# FRONT-UNIT-7.net
KiCad netlist of a schematic drawn in Altium Designer
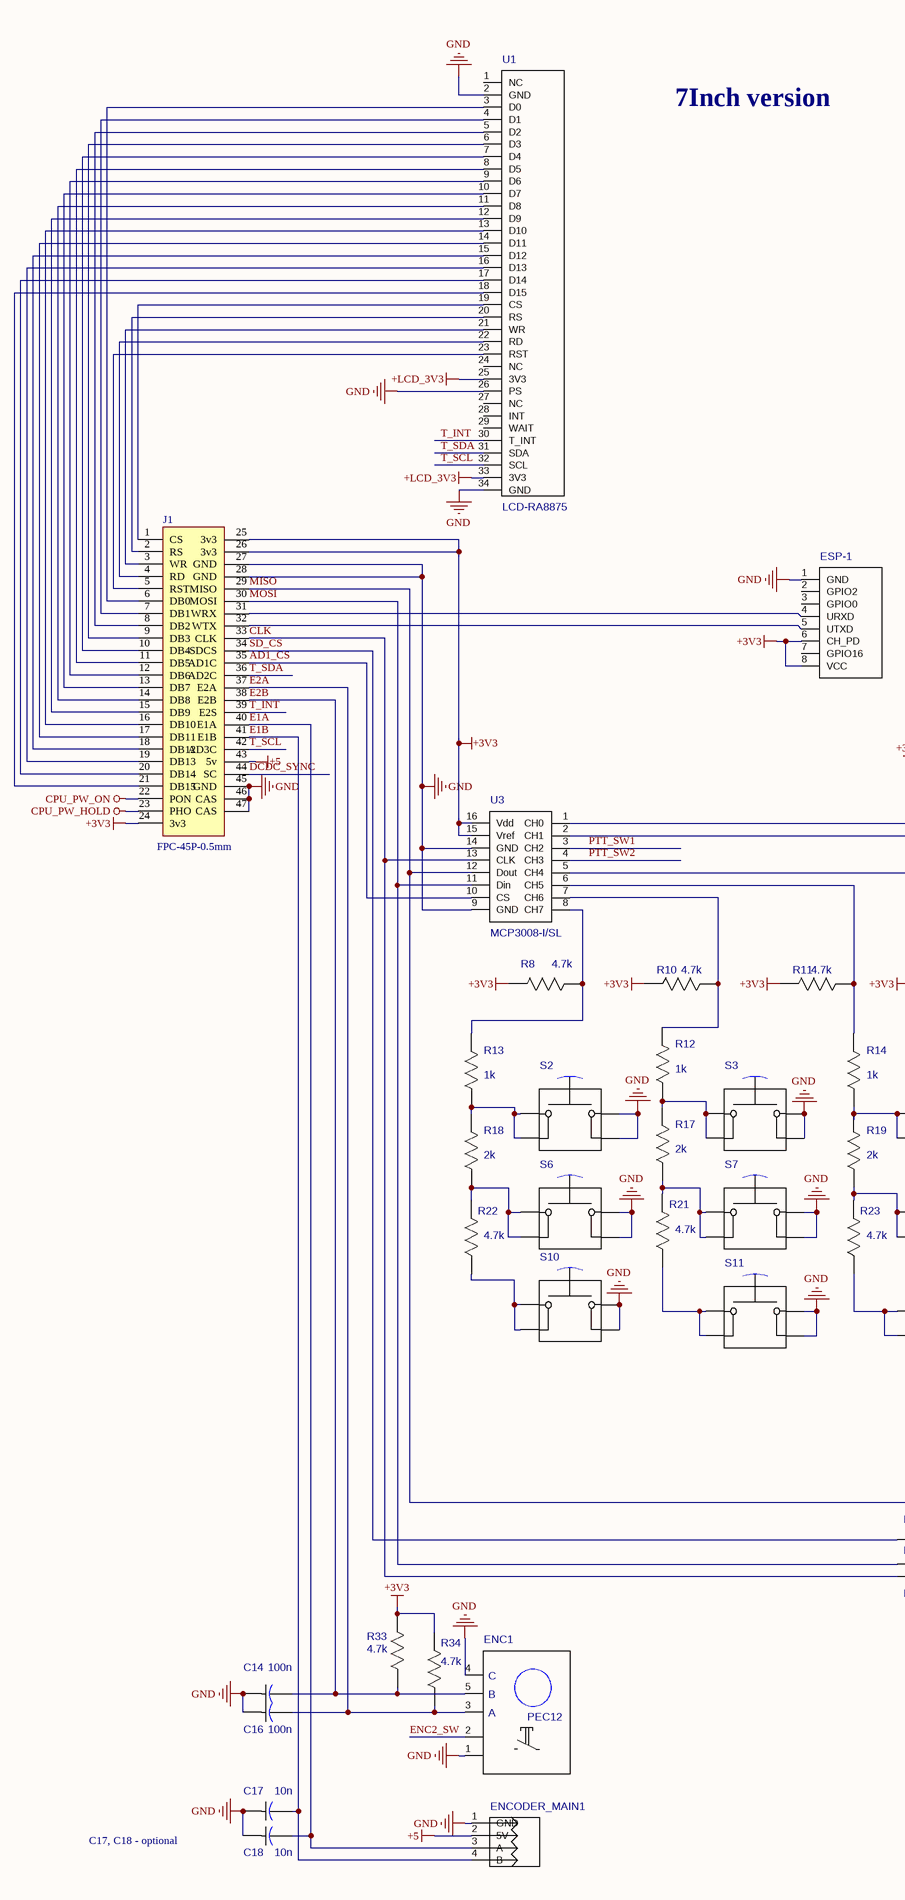
[diagram p0: FRONT-UNIT-7.SCHDOC, left]
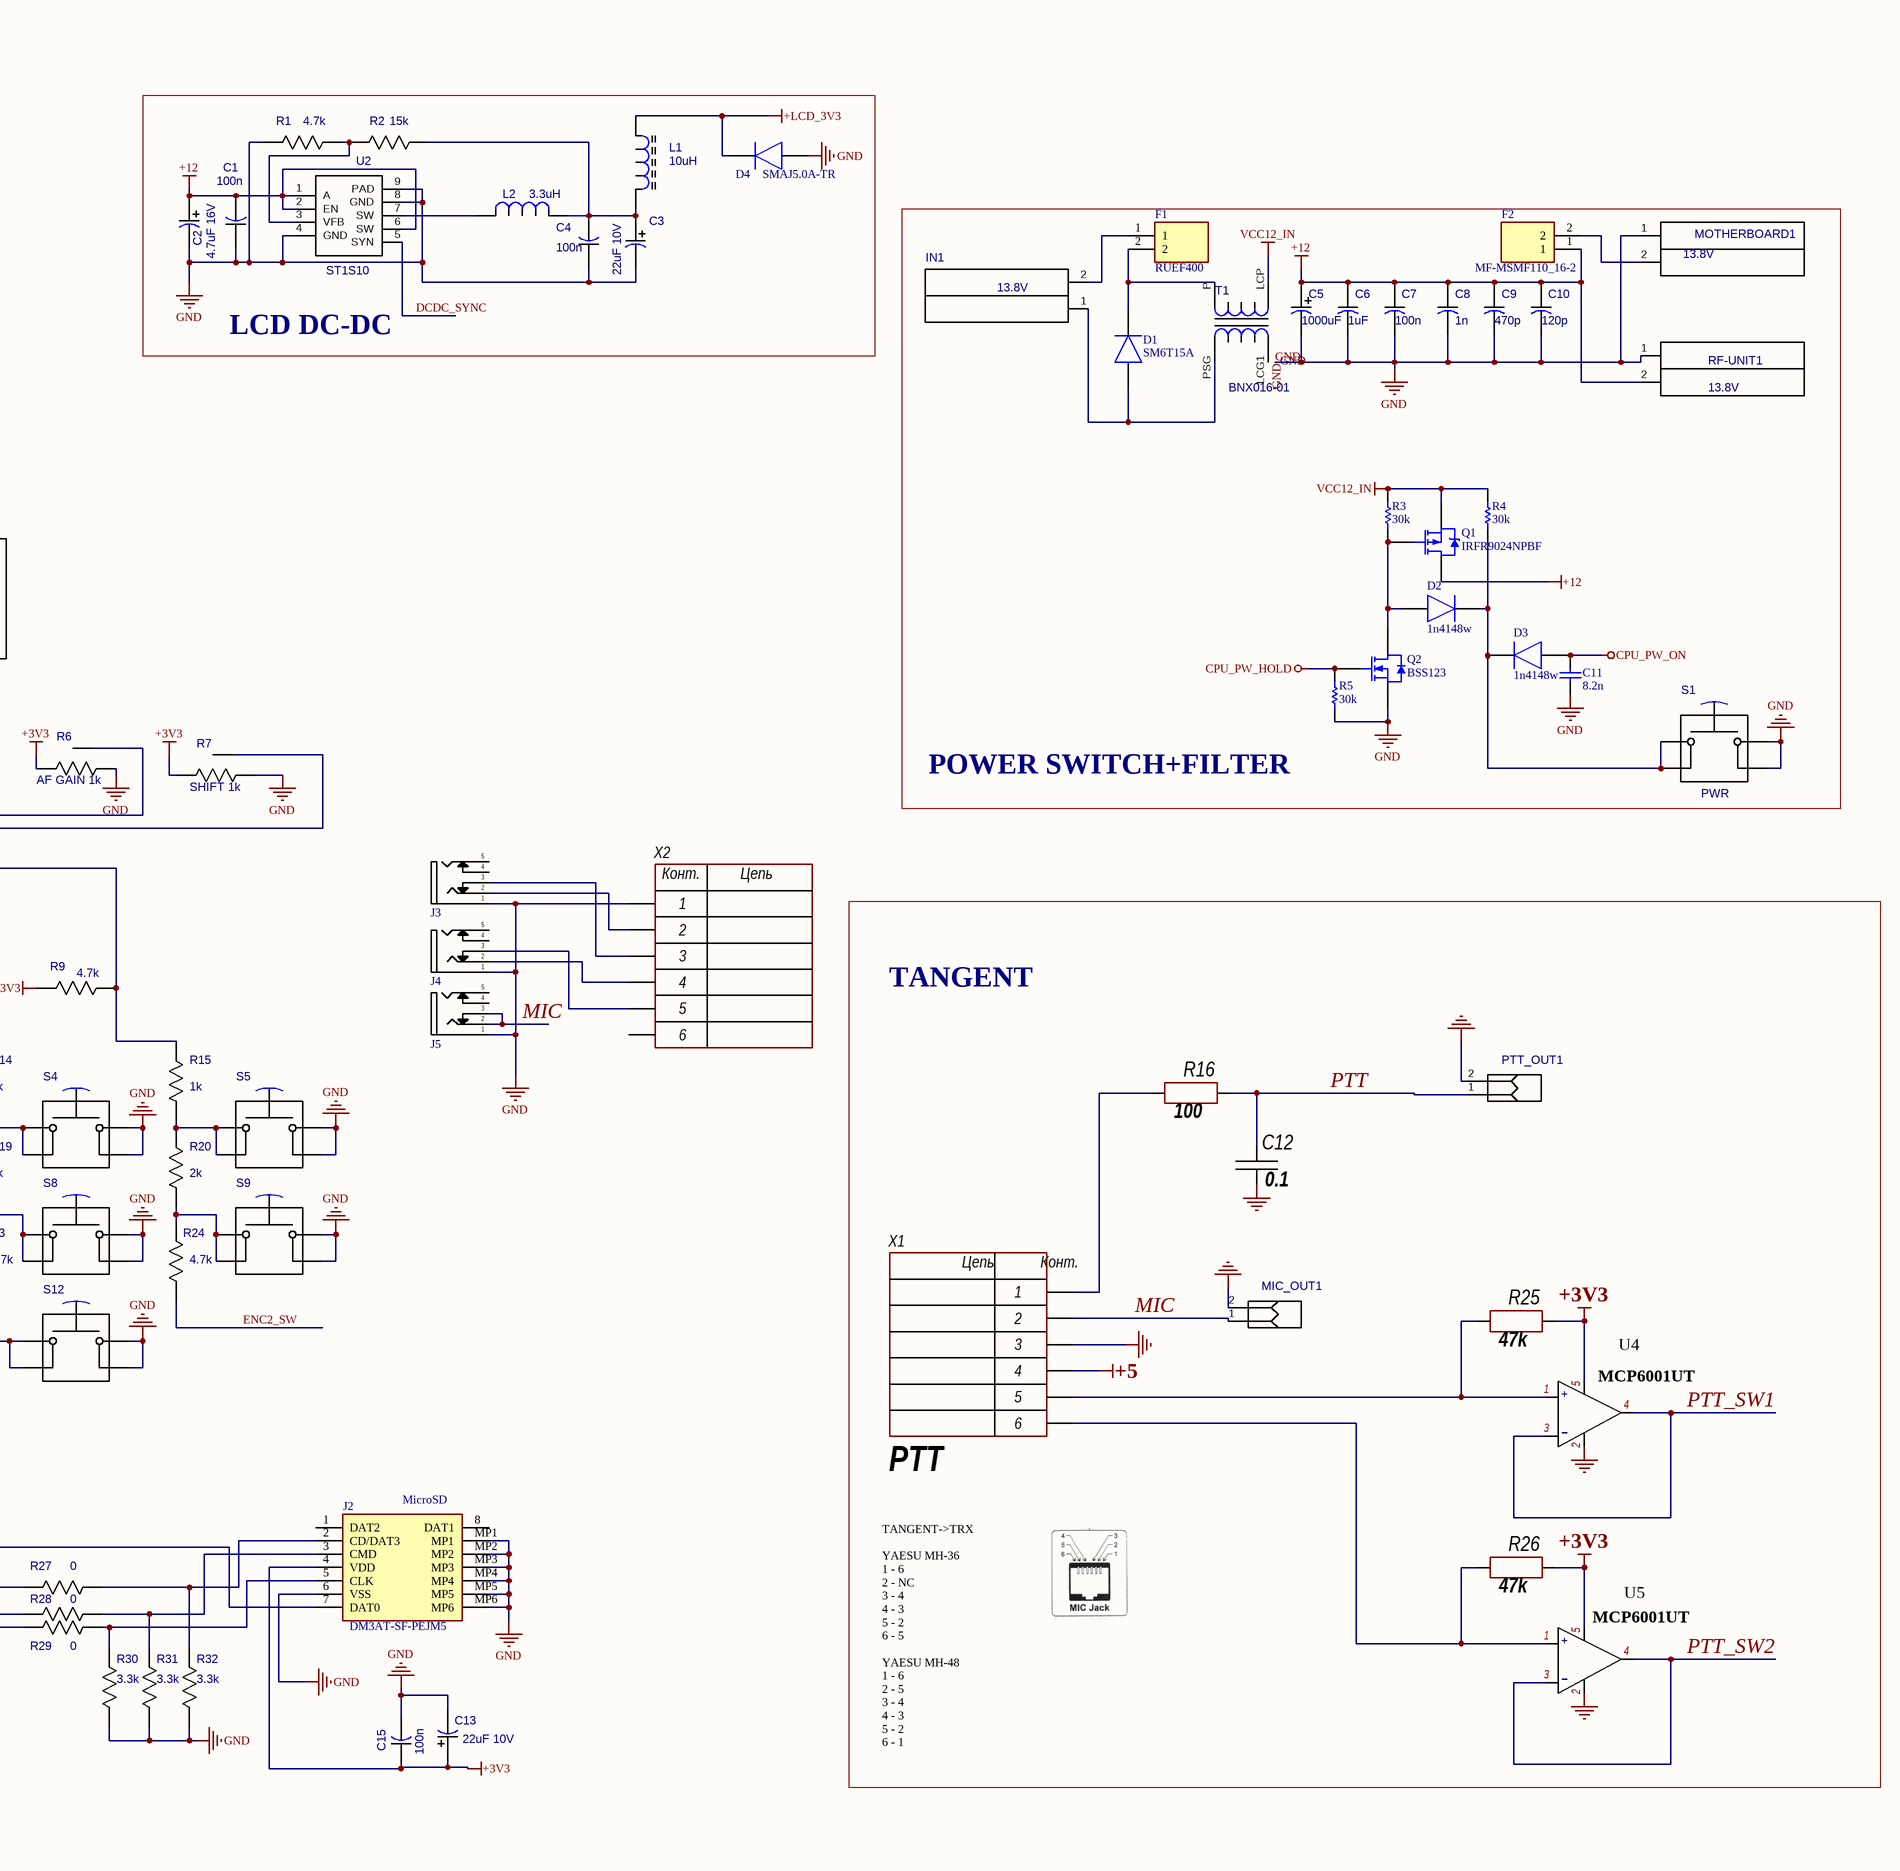
[diagram p1: FRONT-UNIT-7.SCHDOC, right]

(export (version "E")
  (design (tool "Eeschema 10.0.6"))
  (components
    (comp (ref "C1")
      (value "100n")
      (footprint "CAP_0805")
      (description "CAP_0805")
      (libsource (lib "*") (part "CAP_0805"))
    )
    (comp (ref "C2")
      (value "4.7uF 16V")
      (footprint "CAPAE_6.6x6.6h5.4")
      (description "CAPAE_6.6x6.6h5.4")
      (libsource (lib "*") (part "CAPAE_6.6x6.6h5.4"))
    )
    (comp (ref "C3")
      (value "22uF 10V")
      (footprint "CAPAE_4.3x4.3h5.4")
      (description "CAPAE_4.3x4.3h5.4")
      (libsource (lib "*") (part "CAPAE_4.3x4.3h5.4"))
    )
    (comp (ref "C4")
      (value "100n")
      (footprint "CAP_0805")
      (description "CAP_0805")
      (libsource (lib "FRONT-UNIT-7INCH") (part "CAP_0805"))
    )
    (comp (ref "C5")
      (value "1000uF")
      (footprint "CAP250RP")
      (description "CAP250RP")
      (libsource (lib "*") (part "CAP250RP"))
    )
    (comp (ref "C6")
      (value "1uF")
      (footprint "CAP_1206")
      (description "CAP_1206")
      (libsource (lib "*") (part "CAP_1206"))
    )
    (comp (ref "C7")
      (value "100n")
      (footprint "CAP_1206")
      (description "CAP_1206")
      (libsource (lib "*") (part "CAP_1206"))
    )
    (comp (ref "C8")
      (value "1n")
      (footprint "CAP_1206")
      (description "CAP_1206")
      (libsource (lib "*") (part "CAP_1206"))
    )
    (comp (ref "C9")
      (value "470p")
      (footprint "CAP_1206")
      (description "CAP_1206")
      (libsource (lib "*") (part "CAP_1206"))
    )
    (comp (ref "C10")
      (value "120p")
      (footprint "CAP_1206")
      (description "CAP_1206")
      (libsource (lib "FRONT-UNIT-7INCH") (part "CAP_1206"))
    )
    (comp (ref "C11")
      (value "8.2n")
      (footprint "CAPC2013X94X50LL20T25")
      (description "CAP_1206")
      (fields
        (field (name "MANUFACTURER") "AVX Interconnect / Elco")
        (field (name "PART NUMBER") "08055C822KAT2A")
      )
      (libsource (lib "Altium Content Vault") (part "CAP"))
    )
    (comp (ref "C12")
      (value "0.1")
      (footprint "CH0805C")
      (libsource (lib "FRONT-UNIT-7INCH") (part "Capacitor"))
    )
    (comp (ref "C13")
      (value "22uF 10V")
      (footprint "EEEFC_sizeB")
      (description "EEEFC_sizeB")
      (libsource (lib "*") (part "EEEFC_sizeB"))
    )
    (comp (ref "C14")
      (value "100n")
      (footprint "CAP_0805")
      (description "CAP_0805")
      (libsource (lib "*") (part "CAP_0805"))
    )
    (comp (ref "C15")
      (value "100n")
      (footprint "CAP_0805")
      (description "CAP_0805")
      (libsource (lib "*") (part "CAP_0805"))
    )
    (comp (ref "C16")
      (value "100n")
      (footprint "CAP_0805")
      (description "CAP_0805")
      (libsource (lib "*") (part "CAP_0805"))
    )
    (comp (ref "C17")
      (value "10n")
      (footprint "CAP_0805")
      (description "CAP_0805")
      (libsource (lib "*") (part "CAP_0805"))
    )
    (comp (ref "C18")
      (value "10n")
      (footprint "CAP_0805")
      (description "CAP_0805")
      (libsource (lib "*") (part "CAP_0805"))
    )
    (comp (ref "D1")
      (value "SM6T15A")
      (footprint "SamacSys:SMBJ36CATR")
      (description "Diode")
      (fields (field (name "MOUSER PART NUMBER") "511-SM6T15A") (field (name "RS PART NUMBER") "4864915P"))
      (libsource (lib "*") (part "SM6T15A"))
    )
    (comp (ref "D2")
      (value "1n4148w")
      (footprint "SamacSys:SOD3716X135N")
      (description "Diode")
      (libsource (lib "*") (part "1n4148w"))
    )
    (comp (ref "D3")
      (value "1n4148w")
      (footprint "SamacSys:SOD3716X135N")
      (description "Diode")
      (libsource (lib "*") (part "1n4148w"))
    )
    (comp (ref "D4")
      (value "SMAJ5.0A-TR")
      (footprint "SamacSys:SMBJ36CATR")
      (description "Diode")
      (fields
        (field (name "MANUFACTURER_PART_NUMBER") "SMLVT3V3")
        (field (name "MOUSER PART NUMBER") "511-SMLVT3V3")
      )
      (libsource (lib "*") (part "SMLVT3V3"))
    )
    (comp (ref "ENC1") (value "PEC12") (footprint "PEC12") (libsource (lib "*") (part "PEC12")))
    (comp (ref "ENCODER_MAIN1")
      (value "OPTICAL ENCODER")
      (footprint "644456-4")
      (libsource (lib "*") (part "644456-4"))
    )
    (comp (ref "ESP-1")
      (value "ESP-01 ESP8266")
      (footprint "ESP-01 ESP8266")
      (libsource (lib "*") (part "ESP-01 ESP8266"))
    )
    (comp (ref "F1")
      (value "RUEF400")
      (footprint "SamacSys:RUEF400")
      (description "Fuse")
      (fields (field (name "MOUSER PART NUMBER") "650-RUEF400") (field (name "RS PART NUMBER") "5176837P"))
      (libsource (lib "*") (part "RUEF400"))
    )
    (comp (ref "F2")
      (value "MF-MSMF110_16-2")
      (footprint "SamacSys:FUSC4632X85N")
      (description "Fuse")
      (fields
        (field (name "MANUFACTURER_PART_NUMBER") "MF-MSMF110/16-2")
        (field (name "MOUSER PART NUMBER") "652-MF-MSMF110/16-2")
      )
      (libsource (lib "*") (part "MF-MSMF110_16-2"))
    )
    (comp (ref "IN1")
      (value "13.8V")
      (footprint "JX2")
      (description "JX2")
      (libsource (lib "*") (part "JX2"))
    )
    (comp (ref "J1")
      (value "FPC-45P-0.5mm")
      (footprint "FH12S45S05SH60")
      (description "Connector")
      (fields
        (field (name "MANUFACTURER_PART_NUMBER") "FH12S-45S-0.5SH(55)")
        (field (name "MOUSER PART NUMBER") "798-FH12S-45S-05SH55")
      )
      (libsource (lib "*") (part "FH12S-45S-0.5SH_55_"))
    )
    (comp (ref "J2")
      (value "DM3AT-SF-PEJM5")
      (footprint "SamacSys:DM3ATSFPEJM5")
      (description "Connector")
      (libsource (lib "*") (part "DM3AT-SF-PEJM5"))
    )
    (comp (ref "J3") (value "PJ-3,5") (footprint "Audio-PJ-392") (libsource (lib "SDR_ham") (part "PJ-3,5")))
    (comp (ref "J4") (value "PJ-3,5") (footprint "Audio-PJ-392") (libsource (lib "SDR_ham") (part "PJ-3,5")))
    (comp (ref "J5") (value "PJ-3,5") (footprint "Audio-PJ-392") (libsource (lib "SDR_ham") (part "PJ-3,5")))
    (comp (ref "L1")
      (value "10uH")
      (footprint "IND_FERRITE_CORE")
      (description "Inductor")
      (libsource (lib "FRONT-UNIT-7INCH") (part "IND_FERRITE_CORE"))
    )
    (comp (ref "L2")
      (value "3.3uH")
      (footprint "IND_1812")
      (description "IND_1812")
      (libsource (lib "*") (part "IND_1812"))
    )
    (comp (ref "MIC_OUT1")
      (value "MIC_OUT")
      (footprint "51022-0200")
      (description "51022-0200")
      (libsource (lib "*") (part "51022-0200"))
    )
    (comp (ref "MOTHERBOARD1")
      (value "13.8V")
      (footprint "JX2")
      (description "JX2")
      (libsource (lib "*") (part "JX2"))
    )
    (comp (ref "PTT_OUT1")
      (value "PTT_OUT")
      (footprint "51022-0200")
      (description "51022-0200")
      (libsource (lib "*") (part "51022-0200"))
    )
    (comp (ref "Q1")
      (value "IRFR9024NPBF")
      (footprint "ONSC-DPAK-3-369C-01_V")
      (description "IRFR9024NPBF, Транзистор, Р-канал 55В 11А")
      (fields (field (name "MANUFACTURER") "On Semiconductor") (field (name "PARTNUMBER") "NTD2955G"))
      (libsource (lib "Altium Content Vault") (part "ONSC-PMOS-G1S3D4-3_B"))
    )
    (comp (ref "Q2")
      (value "BSS123")
      (footprint "FAIR-SOT23-3_V")
      (fields (field (name "MANUFACTURER") "Fairchild"))
      (libsource (lib "Altium Content Vault") (part "NEMOS-GSD-3"))
    )
    (comp (ref "R1")
      (value "4.7k")
      (footprint "RES_0805")
      (description "RES_0805")
      (libsource (lib "") (part "RES_0805_1"))
    )
    (comp (ref "R2")
      (value "15k")
      (footprint "RES_0805")
      (description "RES_0805")
      (libsource (lib "") (part "RES_0805_1"))
    )
    (comp (ref "R3")
      (value "30k")
      (footprint "RESC2013X60X40NL20T25")
      (description "RES_0805")
      (fields (field (name "MANUFACTURER") "Panasonic") (field (name "PART NUMBER") "ERA-6AEB303V"))
      (libsource (lib "Altium Content Vault") (part "RES"))
    )
    (comp (ref "R4")
      (value "30k")
      (footprint "RESC2013X60X40NL20T25")
      (description "RES_0805")
      (fields (field (name "MANUFACTURER") "Panasonic") (field (name "PART NUMBER") "ERA-6AEB303V"))
      (libsource (lib "Altium Content Vault") (part "RES"))
    )
    (comp (ref "R5")
      (value "30k")
      (footprint "RESC2013X60X40NL20T25")
      (description "RES_0805")
      (fields (field (name "MANUFACTURER") "Panasonic") (field (name "PART NUMBER") "ERA-6AEB303V"))
      (libsource (lib "Altium Content Vault") (part "RES"))
    )
    (comp (ref "R6")
      (value "AF GAIN 1k")
      (footprint "PTV09")
      (description "Adjustable Resistor PTV09")
      (fields (field (name "Comment") "ptv09a-4225f-b102"))
      (libsource (lib "*") (part "PTV09"))
    )
    (comp (ref "R7")
      (value "SHIFT 1k")
      (footprint "PTV09")
      (description "Adjustable Resistor PTV09")
      (fields (field (name "Comment") "ptv09a-4225f-b102"))
      (libsource (lib "*") (part "PTV09"))
    )
    (comp (ref "R8")
      (value "4.7k")
      (footprint "RES_0805")
      (description "RES_0805")
      (libsource (lib "*") (part "RES_0805"))
    )
    (comp (ref "R9")
      (value "4.7k")
      (footprint "RES_0805")
      (description "RES_0805")
      (libsource (lib "*") (part "RES_0805"))
    )
    (comp (ref "R10")
      (value "4.7k")
      (footprint "RES_0805")
      (description "RES_0805")
      (libsource (lib "*") (part "RES_0805"))
    )
    (comp (ref "R11")
      (value "4.7k")
      (footprint "RES_0805")
      (description "RES_0805")
      (libsource (lib "*") (part "RES_0805"))
    )
    (comp (ref "R12")
      (value "1k")
      (footprint "RES_0805")
      (description "RES_0805")
      (libsource (lib "*") (part "RES_0805"))
    )
    (comp (ref "R13")
      (value "1k")
      (footprint "RES_0805")
      (description "RES_0805")
      (libsource (lib "*") (part "RES_0805"))
    )
    (comp (ref "R14")
      (value "1k")
      (footprint "RES_0805")
      (description "RES_0805")
      (libsource (lib "*") (part "RES_0805"))
    )
    (comp (ref "R15")
      (value "1k")
      (footprint "RES_0805")
      (description "RES_0805")
      (libsource (lib "*") (part "RES_0805"))
    )
    (comp (ref "R16")
      (value "100")
      (footprint "FRONT-UNIT-7INCH:CH0805R")
      (libsource (lib "Discrete") (part "Resistor"))
    )
    (comp (ref "R17")
      (value "2k")
      (footprint "RES_0805")
      (description "RES_0805")
      (libsource (lib "*") (part "RES_0805"))
    )
    (comp (ref "R18")
      (value "2k")
      (footprint "RES_0805")
      (description "RES_0805")
      (libsource (lib "*") (part "RES_0805"))
    )
    (comp (ref "R19")
      (value "2k")
      (footprint "RES_0805")
      (description "RES_0805")
      (libsource (lib "*") (part "RES_0805"))
    )
    (comp (ref "R20")
      (value "2k")
      (footprint "RES_0805")
      (description "RES_0805")
      (libsource (lib "*") (part "RES_0805"))
    )
    (comp (ref "R21")
      (value "4.7k")
      (footprint "RES_0805")
      (description "RES_0805")
      (libsource (lib "*") (part "RES_0805"))
    )
    (comp (ref "R22")
      (value "4.7k")
      (footprint "RES_0805")
      (description "RES_0805")
      (libsource (lib "*") (part "RES_0805"))
    )
    (comp (ref "R23")
      (value "4.7k")
      (footprint "RES_0805")
      (description "RES_0805")
      (libsource (lib "*") (part "RES_0805"))
    )
    (comp (ref "R24")
      (value "4.7k")
      (footprint "RES_0805")
      (description "RES_0805")
      (libsource (lib "*") (part "RES_0805"))
    )
    (comp (ref "R25")
      (value "47k")
      (footprint "FRONT-UNIT-7INCH:CH0805R")
      (libsource (lib "Discrete") (part "Resistor"))
    )
    (comp (ref "R26")
      (value "47k")
      (footprint "FRONT-UNIT-7INCH:CH0805C")
      (libsource (lib "Discrete") (part "Resistor"))
    )
    (comp (ref "R27")
      (value "0")
      (footprint "RES_0805")
      (description "RES_0805")
      (libsource (lib "*") (part "RES_0805"))
    )
    (comp (ref "R28")
      (value "0")
      (footprint "RES_0805")
      (description "RES_0805")
      (libsource (lib "*") (part "RES_0805"))
    )
    (comp (ref "R29")
      (value "0")
      (footprint "RES_0805")
      (description "RES_0805")
      (libsource (lib "*") (part "RES_0805"))
    )
    (comp (ref "R30")
      (value "3.3k")
      (footprint "RES_0805")
      (description "RES_0805")
      (libsource (lib "*") (part "RES_0805"))
    )
    (comp (ref "R31")
      (value "3.3k")
      (footprint "RES_0805")
      (description "RES_0805")
      (libsource (lib "*") (part "RES_0805"))
    )
    (comp (ref "R32")
      (value "3.3k")
      (footprint "RES_0805")
      (description "RES_0805")
      (libsource (lib "*") (part "RES_0805"))
    )
    (comp (ref "R33")
      (value "4.7k")
      (footprint "RES_0805")
      (description "RES_0805")
      (libsource (lib "*") (part "RES_0805"))
    )
    (comp (ref "R34")
      (value "4.7k")
      (footprint "RES_0805")
      (description "RES_0805")
      (libsource (lib "*") (part "RES_0805"))
    )
    (comp (ref "RF-UNIT1")
      (value "13.8V")
      (footprint "JX2")
      (description "JX2")
      (libsource (lib "*") (part "JX2"))
    )
    (comp (ref "S1")
      (value "PWR")
      (footprint "PTS645SK50LFS")
      (description "PTS645SK50LFS")
      (libsource (lib "*") (part "PTS645SK50LFS"))
    )
    (comp (ref "S2")
      (value "PTS645SK50LFS")
      (footprint "PTS645SK50LFS")
      (fields (field (name "LCSC PART #") "test"))
      (libsource (lib "*") (part "PTS645SK50LFS"))
    )
    (comp (ref "S3")
      (value "PTS645SK50LFS")
      (footprint "PTS645SK50LFS")
      (libsource (lib "*") (part "PTS645SK50LFS"))
    )
    (comp (ref "S4")
      (value "PTS645SK50LFS")
      (footprint "PTS645SK50LFS")
      (libsource (lib "*") (part "PTS645SK50LFS"))
    )
    (comp (ref "S5")
      (value "PTS645SK50LFS")
      (footprint "PTS645SK50LFS")
      (libsource (lib "*") (part "PTS645SK50LFS"))
    )
    (comp (ref "S6")
      (value "PTS645SK50LFS")
      (footprint "PTS645SK50LFS")
      (libsource (lib "*") (part "PTS645SK50LFS"))
    )
    (comp (ref "S7")
      (value "PTS645SK50LFS")
      (footprint "PTS645SK50LFS")
      (libsource (lib "*") (part "PTS645SK50LFS"))
    )
    (comp (ref "S8")
      (value "PTS645SK50LFS")
      (footprint "PTS645SK50LFS")
      (libsource (lib "*") (part "PTS645SK50LFS"))
    )
    (comp (ref "S9")
      (value "PTS645SK50LFS")
      (footprint "PTS645SK50LFS")
      (libsource (lib "*") (part "PTS645SK50LFS"))
    )
    (comp (ref "S10")
      (value "PTS645SK50LFS")
      (footprint "PTS645SK50LFS")
      (libsource (lib "*") (part "PTS645SK50LFS"))
    )
    (comp (ref "S11")
      (value "PTS645SK50LFS")
      (footprint "PTS645SK50LFS")
      (libsource (lib "*") (part "PTS645SK50LFS"))
    )
    (comp (ref "S12")
      (value "PTS645SK50LFS")
      (footprint "PTS645SK50LFS")
      (libsource (lib "*") (part "PTS645SK50LFS"))
    )
    (comp (ref "T1")
      (value "BNX016-01")
      (footprint "TRANSF_ICORE")
      (libsource (lib "*") (part "TRANSF_ICORE"))
    )
    (comp (ref "U1")
      (value "LCD-RA8875")
      (footprint "LCD-RA8875")
      (libsource (lib "FRONT-UNIT-7INCH") (part "LCD-RA8875"))
    )
    (comp (ref "U2") (value "ST1S10") (footprint "ST1S10") (libsource (lib "*") (part "ST1S10")))
    (comp (ref "U3")
      (value "MCP3008-I/SL")
      (footprint "MCP3008-I/SL")
      (libsource (lib "*") (part "MCP3008-I/SL"))
    )
    (comp (ref "U4")
      (value "MCP6001UT")
      (footprint "SOT23-5")
      (libsource (lib "Analog") (part "MCP6001UT_1"))
    )
    (comp (ref "U5")
      (value "MCP6001UT")
      (footprint "SOT23-5")
      (libsource (lib "Analog") (part "MCP6001UT_1"))
    )
    (comp (ref "X1")
      (value "PTT")
      (footprint "custom:CON: PLS-6")
      (libsource (lib "Connectors") (part "6-Connector"))
    )
    (comp (ref "X2")
      (value "PTT")
      (footprint "custom:CON: PLS-6")
      (libsource (lib "") (part "6-Connector_1"))
    )
  )
  (nets
    (net (code "1") (name "+3V3") (class "Default")
      (node (ref "C13") (pin "1") (pinfunction "PLUS_1") (pintype "passive"))
      (node (ref "C15") (pin "1") (pinfunction "1_1") (pintype "passive"))
      (node (ref "ESP-1") (pin "6") (pinfunction "CH_PD_6") (pintype "passive"))
      (node (ref "ESP-1") (pin "8") (pinfunction "VCC_8") (pintype "passive"))
      (node (ref "J1") (pin "24") (pinfunction "3v3_24") (pintype "passive"))
      (node (ref "J1") (pin "25") (pinfunction "3v3_25") (pintype "passive"))
      (node (ref "J1") (pin "26") (pinfunction "3v3_26") (pintype "passive"))
      (node (ref "J2") (pin "4") (pinfunction "VDD_4") (pintype "passive"))
      (node (ref "R10") (pin "2") (pinfunction "2_2") (pintype "passive"))
      (node (ref "R11") (pin "2") (pinfunction "2_2") (pintype "passive"))
      (node (ref "R25") (pin "2") (pinfunction "2_2") (pintype "passive"))
      (node (ref "R26") (pin "2") (pinfunction "2_2") (pintype "passive"))
      (node (ref "R33") (pin "2") (pinfunction "2_2") (pintype "passive"))
      (node (ref "R34") (pin "2") (pinfunction "2_2") (pintype "passive"))
      (node (ref "R6") (pin "1") (pinfunction "CW_1") (pintype "passive"))
      (node (ref "R7") (pin "1") (pinfunction "CW_1") (pintype "passive"))
      (node (ref "R8") (pin "2") (pinfunction "2_2") (pintype "passive"))
      (node (ref "R9") (pin "2") (pinfunction "2_2") (pintype "passive"))
      (node (ref "U3") (pin "15") (pinfunction "Vref_15") (pintype "passive"))
      (node (ref "U3") (pin "16") (pinfunction "Vdd_16") (pintype "passive"))
      (node (ref "U4") (pin "5") (pinfunction "5_5") (pintype "passive"))
      (node (ref "U5") (pin "5") (pinfunction "5_5") (pintype "passive"))
    )
    (net (code "2") (name "+5") (class "Default")
      (node (ref "ENCODER_MAIN1") (pin "2") (pinfunction "5V_2") (pintype "passive"))
      (node (ref "J1") (pin "43") (pinfunction "5v_43") (pintype "passive"))
      (node (ref "X1") (pin "4") (pinfunction "4_4") (pintype "power_in"))
    )
    (net (code "3") (name "+12") (class "Default")
      (node (ref "C1") (pin "2") (pinfunction "2_2") (pintype "passive"))
      (node (ref "C10") (pin "1") (pinfunction "1_1") (pintype "passive"))
      (node (ref "C2") (pin "1") (pinfunction "PLUS_1") (pintype "passive"))
      (node (ref "C5") (pin "1") (pinfunction "PLUS_1") (pintype "passive"))
      (node (ref "C6") (pin "1") (pinfunction "1_1") (pintype "passive"))
      (node (ref "C7") (pin "1") (pinfunction "1_1") (pintype "passive"))
      (node (ref "C8") (pin "1") (pinfunction "1_1") (pintype "passive"))
      (node (ref "C9") (pin "1") (pinfunction "1_1") (pintype "passive"))
      (node (ref "F2") (pin "1") (pinfunction "1_1") (pintype "passive"))
      (node (ref "Q1") (pin "4") (pinfunction "D_4") (pintype "passive"))
      (node (ref "RF-UNIT1") (pin "2") (pinfunction "1_2") (pintype "passive"))
      (node (ref "U2") (pin "1") (pinfunction "A_1") (pintype "passive"))
      (node (ref "U2") (pin "2") (pinfunction "EN_2") (pintype "passive"))
      (node (ref "U2") (pin "6") (pinfunction "SW_6") (pintype "passive"))
    )
    (net (code "4") (name "+LCD_3V3") (class "Default")
      (node (ref "D4") (pin "1") (pinfunction "K_1") (pintype "passive"))
      (node (ref "L1") (pin "1") (pinfunction "A_1") (pintype "passive"))
      (node (ref "U1") (pin "25") (pinfunction "3V3_25") (pintype "passive"))
      (node (ref "U1") (pin "33") (pinfunction "3V3_33") (pintype "passive"))
    )
    (net (code "5") (name "/AD1_CS") (class "Default")
      (node (ref "J1") (pin "35") (pinfunction "AD1C_35") (pintype "passive"))
      (node (ref "U3") (pin "10") (pinfunction "CS_10") (pintype "passive"))
    )
    (net (code "6") (name "/CLK") (class "Default")
      (node (ref "J1") (pin "33") (pinfunction "CLK_33") (pintype "passive"))
      (node (ref "R29") (pin "2") (pinfunction "2_2") (pintype "passive"))
      (node (ref "U3") (pin "13") (pinfunction "CLK_13") (pintype "passive"))
    )
    (net (code "7") (name "/DCDC_SYNC") (class "Default")
      (node (ref "J1") (pin "44") (pinfunction "SC_44") (pintype "passive"))
      (node (ref "U2") (pin "5") (pinfunction "SYN_5") (pintype "passive"))
    )
    (net (code "8") (name "/E1A") (class "Default")
      (node (ref "C18") (pin "2") (pinfunction "2_2") (pintype "passive"))
      (node (ref "ENCODER_MAIN1") (pin "3") (pinfunction "A_3") (pintype "passive"))
      (node (ref "J1") (pin "40") (pinfunction "E1A_40") (pintype "passive"))
    )
    (net (code "9") (name "/E1B") (class "Default")
      (node (ref "C17") (pin "2") (pinfunction "2_2") (pintype "passive"))
      (node (ref "ENCODER_MAIN1") (pin "4") (pinfunction "B_4") (pintype "passive"))
      (node (ref "J1") (pin "41") (pinfunction "E1B_41") (pintype "passive"))
    )
    (net (code "10") (name "/E2A") (class "Default")
      (node (ref "C16") (pin "2") (pinfunction "2_2") (pintype "passive"))
      (node (ref "ENC1") (pin "3") (pinfunction "A_3") (pintype "passive"))
      (node (ref "J1") (pin "37") (pinfunction "E2A_37") (pintype "passive"))
      (node (ref "R34") (pin "1") (pinfunction "1_1") (pintype "passive"))
    )
    (net (code "11") (name "/E2B") (class "Default")
      (node (ref "C14") (pin "2") (pinfunction "2_2") (pintype "passive"))
      (node (ref "ENC1") (pin "5") (pinfunction "B_5") (pintype "passive"))
      (node (ref "J1") (pin "38") (pinfunction "E2B_38") (pintype "passive"))
      (node (ref "R33") (pin "1") (pinfunction "1_1") (pintype "passive"))
    )
    (net (code "12") (name "/ENC2_SW") (class "Default")
      (node (ref "ENC1") (pin "2") (pinfunction "2_2") (pintype "passive"))
      (node (ref "R24") (pin "1") (pinfunction "1_1") (pintype "passive"))
    )
    (net (code "13") (name "/MIC") (class "Default")
      (node (ref "J5") (pin "2") (pinfunction "7_2") (pintype "passive"))
      (node (ref "J5") (pin "3") (pinfunction "6_3") (pintype "passive"))
      (node (ref "MIC_OUT1") (pin "1") (pinfunction "1_1") (pintype "passive"))
      (node (ref "X1") (pin "2") (pinfunction "2_2") (pintype "passive"))
    )
    (net (code "14") (name "/MISO") (class "Default")
      (node (ref "J1") (pin "29") (pinfunction "MISO_29") (pintype "passive"))
      (node (ref "J2") (pin "7") (pinfunction "DAT0_7") (pintype "passive"))
      (node (ref "U3") (pin "12") (pinfunction "Dout_12") (pintype "passive"))
    )
    (net (code "15") (name "/MOSI") (class "Default")
      (node (ref "J1") (pin "30") (pinfunction "MOSI_30") (pintype "passive"))
      (node (ref "R28") (pin "2") (pinfunction "2_2") (pintype "passive"))
      (node (ref "U3") (pin "11") (pinfunction "Din_11") (pintype "passive"))
    )
    (net (code "16") (name "/PTT") (class "Default")
      (node (ref "C12") (pin "2") (pinfunction "2_2") (pintype "power_in"))
      (node (ref "PTT_OUT1") (pin "1") (pinfunction "1_1") (pintype "passive"))
      (node (ref "R16") (pin "2") (pinfunction "2_2") (pintype "passive"))
    )
    (net (code "17") (name "/PTT_SW1") (class "Default")
      (node (ref "U3") (pin "3") (pinfunction "CH2_3") (pintype "passive"))
      (node (ref "U4") (pin "3") (pinfunction "3_3") (pintype "passive"))
      (node (ref "U4") (pin "4") (pinfunction "4_4") (pintype "passive"))
    )
    (net (code "18") (name "/PTT_SW2") (class "Default")
      (node (ref "U3") (pin "4") (pinfunction "CH3_4") (pintype "passive"))
      (node (ref "U5") (pin "3") (pinfunction "3_3") (pintype "passive"))
      (node (ref "U5") (pin "4") (pinfunction "4_4") (pintype "passive"))
    )
    (net (code "19") (name "/SD_CS") (class "Default")
      (node (ref "J1") (pin "34") (pinfunction "SDCS_34") (pintype "passive"))
      (node (ref "R27") (pin "2") (pinfunction "2_2") (pintype "passive"))
    )
    (net (code "20") (name "/T_INT") (class "Default")
      (node (ref "J1") (pin "39") (pinfunction "E2S_39") (pintype "passive"))
      (node (ref "U1") (pin "30") (pinfunction "T_INT_30") (pintype "passive"))
    )
    (net (code "21") (name "/T_SCL") (class "Default")
      (node (ref "J1") (pin "42") (pinfunction "AD3C_42") (pintype "passive"))
      (node (ref "U1") (pin "32") (pinfunction "SCL_32") (pintype "passive"))
    )
    (net (code "22") (name "/T_SDA") (class "Default")
      (node (ref "J1") (pin "36") (pinfunction "AD2C_36") (pintype "passive"))
      (node (ref "U1") (pin "31") (pinfunction "SDA_31") (pintype "passive"))
    )
    (net (code "23") (name "CPU_PW_HOLD") (class "Default")
      (node (ref "J1") (pin "23") (pinfunction "PHO_23") (pintype "passive"))
      (node (ref "Q2") (pin "1") (pinfunction "G_1") (pintype "passive"))
      (node (ref "R5") (pin "2") (pinfunction "2_2") (pintype "passive"))
    )
    (net (code "24") (name "CPU_PW_ON") (class "Default")
      (node (ref "C11") (pin "2") (pinfunction "2_2") (pintype "passive"))
      (node (ref "D3") (pin "2") (pinfunction "A_2") (pintype "passive"))
      (node (ref "J1") (pin "22") (pinfunction "PON_22") (pintype "passive"))
    )
    (net (code "25") (name "GND") (class "Default")
      (node (ref "C1") (pin "1") (pinfunction "1_1") (pintype "passive"))
      (node (ref "C10") (pin "2") (pinfunction "2_2") (pintype "passive"))
      (node (ref "C11") (pin "1") (pinfunction "1_1") (pintype "passive"))
      (node (ref "C12") (pin "1") (pinfunction "1_1") (pintype "power_in"))
      (node (ref "C13") (pin "2") (pinfunction "MINUS_2") (pintype "passive"))
      (node (ref "C14") (pin "1") (pinfunction "1_1") (pintype "passive"))
      (node (ref "C15") (pin "2") (pinfunction "2_2") (pintype "passive"))
      (node (ref "C16") (pin "1") (pinfunction "1_1") (pintype "passive"))
      (node (ref "C17") (pin "1") (pinfunction "1_1") (pintype "passive"))
      (node (ref "C18") (pin "1") (pinfunction "1_1") (pintype "passive"))
      (node (ref "C2") (pin "2") (pinfunction "MINUS_2") (pintype "passive"))
      (node (ref "C3") (pin "2") (pinfunction "MINUS_2") (pintype "passive"))
      (node (ref "C4") (pin "1") (pinfunction "1_1") (pintype "passive"))
      (node (ref "C5") (pin "2") (pinfunction "MINUS_2") (pintype "passive"))
      (node (ref "C6") (pin "2") (pinfunction "2_2") (pintype "passive"))
      (node (ref "C7") (pin "2") (pinfunction "2_2") (pintype "passive"))
      (node (ref "C8") (pin "2") (pinfunction "2_2") (pintype "passive"))
      (node (ref "C9") (pin "2") (pinfunction "2_2") (pintype "passive"))
      (node (ref "D4") (pin "2") (pinfunction "A_2") (pintype "passive"))
      (node (ref "ENC1") (pin "1") (pinfunction "1_1") (pintype "passive"))
      (node (ref "ENC1") (pin "4") (pinfunction "C_4") (pintype "passive"))
      (node (ref "ENCODER_MAIN1") (pin "1") (pinfunction "GND_1") (pintype "passive"))
      (node (ref "ESP-1") (pin "1") (pinfunction "GND_1") (pintype "passive"))
      (node (ref "J1") (pin "27") (pinfunction "GND_27") (pintype "passive"))
      (node (ref "J1") (pin "28") (pinfunction "GND_28") (pintype "passive"))
      (node (ref "J1") (pin "45") (pinfunction "GND_45") (pintype "passive"))
      (node (ref "J1") (pin "46") (pinfunction "CAS_46") (pintype "passive"))
      (node (ref "J1") (pin "47") (pinfunction "CAS_47") (pintype "passive"))
      (node (ref "J2") (pin "6") (pinfunction "VSS_6") (pintype "passive"))
      (node (ref "J2") (pin "MP1") (pinfunction "MP1_MP1") (pintype "passive"))
      (node (ref "J2") (pin "MP2") (pinfunction "MP2_MP2") (pintype "passive"))
      (node (ref "J2") (pin "MP3") (pinfunction "MP3_MP3") (pintype "passive"))
      (node (ref "J2") (pin "MP4") (pinfunction "MP4_MP4") (pintype "passive"))
      (node (ref "J2") (pin "MP5") (pinfunction "MP5_MP5") (pintype "passive"))
      (node (ref "J2") (pin "MP6") (pinfunction "MP6_MP6") (pintype "passive"))
      (node (ref "J3") (pin "1") (pinfunction "8_1") (pintype "passive"))
      (node (ref "J4") (pin "1") (pinfunction "8_1") (pintype "passive"))
      (node (ref "J5") (pin "1") (pinfunction "8_1") (pintype "passive"))
      (node (ref "MIC_OUT1") (pin "2") (pinfunction "2_2") (pintype "passive"))
      (node (ref "MOTHERBOARD1") (pin "1") (pinfunction "2_1") (pintype "passive"))
      (node (ref "PTT_OUT1") (pin "2") (pinfunction "2_2") (pintype "passive"))
      (node (ref "Q2") (pin "2") (pinfunction "S_2") (pintype "passive"))
      (node (ref "R1") (pin "1") (pinfunction "1_1") (pintype "passive"))
      (node (ref "R30") (pin "1") (pinfunction "1_1") (pintype "passive"))
      (node (ref "R31") (pin "1") (pinfunction "1_1") (pintype "passive"))
      (node (ref "R32") (pin "1") (pinfunction "1_1") (pintype "passive"))
      (node (ref "R5") (pin "1") (pinfunction "1_1") (pintype "passive"))
      (node (ref "R6") (pin "3") (pinfunction "CCW_3") (pintype "passive"))
      (node (ref "R7") (pin "3") (pinfunction "CCW_3") (pintype "passive"))
      (node (ref "RF-UNIT1") (pin "1") (pinfunction "2_1") (pintype "passive"))
      (node (ref "S1") (pin "3") (pinfunction "B_3") (pintype "passive"))
      (node (ref "S1") (pin "4") (pinfunction "B_4") (pintype "passive"))
      (node (ref "S10") (pin "3") (pinfunction "B_3") (pintype "passive"))
      (node (ref "S10") (pin "4") (pinfunction "B_4") (pintype "passive"))
      (node (ref "S11") (pin "3") (pinfunction "B_3") (pintype "passive"))
      (node (ref "S11") (pin "4") (pinfunction "B_4") (pintype "passive"))
      (node (ref "S12") (pin "3") (pinfunction "B_3") (pintype "passive"))
      (node (ref "S12") (pin "4") (pinfunction "B_4") (pintype "passive"))
      (node (ref "S2") (pin "3") (pinfunction "B_3") (pintype "passive"))
      (node (ref "S2") (pin "4") (pinfunction "B_4") (pintype "passive"))
      (node (ref "S3") (pin "3") (pinfunction "B_3") (pintype "passive"))
      (node (ref "S3") (pin "4") (pinfunction "B_4") (pintype "passive"))
      (node (ref "S4") (pin "3") (pinfunction "B_3") (pintype "passive"))
      (node (ref "S4") (pin "4") (pinfunction "B_4") (pintype "passive"))
      (node (ref "S5") (pin "3") (pinfunction "B_3") (pintype "passive"))
      (node (ref "S5") (pin "4") (pinfunction "B_4") (pintype "passive"))
      (node (ref "S6") (pin "3") (pinfunction "B_3") (pintype "passive"))
      (node (ref "S6") (pin "4") (pinfunction "B_4") (pintype "passive"))
      (node (ref "S7") (pin "3") (pinfunction "B_3") (pintype "passive"))
      (node (ref "S7") (pin "4") (pinfunction "B_4") (pintype "passive"))
      (node (ref "S8") (pin "3") (pinfunction "B_3") (pintype "passive"))
      (node (ref "S8") (pin "4") (pinfunction "B_4") (pintype "passive"))
      (node (ref "S9") (pin "3") (pinfunction "B_3") (pintype "passive"))
      (node (ref "S9") (pin "4") (pinfunction "B_4") (pintype "passive"))
      (node (ref "T1") (pin "LCG1") (pinfunction "S2_LCG1") (pintype "passive"))
      (node (ref "U1") (pin "2") (pinfunction "GND_2") (pintype "passive"))
      (node (ref "U1") (pin "26") (pinfunction "PS_26") (pintype "passive"))
      (node (ref "U1") (pin "34") (pinfunction "GND_34") (pintype "passive"))
      (node (ref "U2") (pin "4") (pinfunction "GND_4") (pintype "passive"))
      (node (ref "U2") (pin "8") (pinfunction "GND_8") (pintype "passive"))
      (node (ref "U2") (pin "9") (pinfunction "PAD_9") (pintype "passive"))
      (node (ref "U3") (pin "14") (pinfunction "GND_14") (pintype "passive"))
      (node (ref "U3") (pin "9") (pinfunction "GND_9") (pintype "passive"))
      (node (ref "U4") (pin "2") (pinfunction "2_2") (pintype "passive"))
      (node (ref "U5") (pin "2") (pinfunction "2_2") (pintype "passive"))
      (node (ref "X1") (pin "3") (pinfunction "3_3") (pintype "power_in"))
      (node (ref "X2") (pin "1") (pinfunction "1_1") (pintype "passive"))
    )
    (net (code "26") (name "Net-(C3-PLUS)") (class "Default")
      (node (ref "C3") (pin "1") (pinfunction "PLUS_1") (pintype "passive"))
      (node (ref "C4") (pin "2") (pinfunction "2_2") (pintype "passive"))
      (node (ref "L1") (pin "2") (pinfunction "B_2") (pintype "passive"))
      (node (ref "L2") (pin "2") (pinfunction "2_2") (pintype "passive"))
      (node (ref "R2") (pin "2") (pinfunction "2_2") (pintype "passive"))
    )
    (net (code "27") (name "Net-(D1-A)") (class "Default")
      (node (ref "D1") (pin "2") (pinfunction "A_2") (pintype "passive"))
      (node (ref "IN1") (pin "1") (pinfunction "2_1") (pintype "passive"))
      (node (ref "T1") (pin "PSG") (pinfunction "S1_PSG") (pintype "passive"))
    )
    (net (code "28") (name "Net-(D1-K)") (class "Default")
      (node (ref "D1") (pin "1") (pinfunction "K_1") (pintype "passive"))
      (node (ref "F1") (pin "2") (pinfunction "2_2") (pintype "passive"))
      (node (ref "T1") (pin "P") (pinfunction "P1_P") (pintype "passive"))
    )
    (net (code "29") (name "Net-(D2-A)") (class "Default")
      (node (ref "D2") (pin "2") (pinfunction "A_2") (pintype "passive"))
      (node (ref "Q1") (pin "1") (pinfunction "G_1") (pintype "passive"))
      (node (ref "Q2") (pin "3") (pinfunction "D_3") (pintype "passive"))
      (node (ref "R3") (pin "1") (pinfunction "1_1") (pintype "passive"))
    )
    (net (code "30") (name "Net-(D2-K)") (class "Default")
      (node (ref "D2") (pin "1") (pinfunction "K_1") (pintype "passive"))
      (node (ref "D3") (pin "1") (pinfunction "K_1") (pintype "passive"))
      (node (ref "R4") (pin "1") (pinfunction "1_1") (pintype "passive"))
      (node (ref "S1") (pin "1") (pinfunction "A_1") (pintype "passive"))
      (node (ref "S1") (pin "2") (pinfunction "A_2") (pintype "passive"))
    )
    (net (code "31") (name "Net-(ESP-1-URXD)") (class "Default")
      (node (ref "ESP-1") (pin "4") (pinfunction "URXD_4") (pintype "passive"))
      (node (ref "J1") (pin "31") (pinfunction "WRX_31") (pintype "passive"))
    )
    (net (code "32") (name "Net-(ESP-1-UTXD)") (class "Default")
      (node (ref "ESP-1") (pin "5") (pinfunction "UTXD_5") (pintype "passive"))
      (node (ref "J1") (pin "32") (pinfunction "WTX_32") (pintype "passive"))
    )
    (net (code "33") (name "Net-(IN1-1)") (class "Default")
      (node (ref "F1") (pin "1") (pinfunction "1_1") (pintype "passive"))
      (node (ref "IN1") (pin "2") (pinfunction "1_2") (pintype "passive"))
    )
    (net (code "34") (name "Net-(J1-CS)") (class "Default")
      (node (ref "J1") (pin "1") (pinfunction "CS_1") (pintype "passive"))
      (node (ref "U1") (pin "19") (pinfunction "CS_19") (pintype "passive"))
    )
    (net (code "35") (name "Net-(J1-DB0)") (class "Default")
      (node (ref "J1") (pin "6") (pinfunction "DB0_6") (pintype "passive"))
      (node (ref "U1") (pin "3") (pinfunction "D0_3") (pintype "passive"))
    )
    (net (code "36") (name "Net-(J1-DB1)") (class "Default")
      (node (ref "J1") (pin "7") (pinfunction "DB1_7") (pintype "passive"))
      (node (ref "U1") (pin "4") (pinfunction "D1_4") (pintype "passive"))
    )
    (net (code "37") (name "Net-(J1-DB2)") (class "Default")
      (node (ref "J1") (pin "8") (pinfunction "DB2_8") (pintype "passive"))
      (node (ref "U1") (pin "5") (pinfunction "D2_5") (pintype "passive"))
    )
    (net (code "38") (name "Net-(J1-DB3)") (class "Default")
      (node (ref "J1") (pin "9") (pinfunction "DB3_9") (pintype "passive"))
      (node (ref "U1") (pin "6") (pinfunction "D3_6") (pintype "passive"))
    )
    (net (code "39") (name "Net-(J1-DB4)") (class "Default")
      (node (ref "J1") (pin "10") (pinfunction "DB4_10") (pintype "passive"))
      (node (ref "U1") (pin "7") (pinfunction "D4_7") (pintype "passive"))
    )
    (net (code "40") (name "Net-(J1-DB5)") (class "Default")
      (node (ref "J1") (pin "11") (pinfunction "DB5_11") (pintype "passive"))
      (node (ref "U1") (pin "8") (pinfunction "D5_8") (pintype "passive"))
    )
    (net (code "41") (name "Net-(J1-DB6)") (class "Default")
      (node (ref "J1") (pin "12") (pinfunction "DB6_12") (pintype "passive"))
      (node (ref "U1") (pin "9") (pinfunction "D6_9") (pintype "passive"))
    )
    (net (code "42") (name "Net-(J1-DB7)") (class "Default")
      (node (ref "J1") (pin "13") (pinfunction "DB7_13") (pintype "passive"))
      (node (ref "U1") (pin "10") (pinfunction "D7_10") (pintype "passive"))
    )
    (net (code "43") (name "Net-(J1-DB8)") (class "Default")
      (node (ref "J1") (pin "14") (pinfunction "DB8_14") (pintype "passive"))
      (node (ref "U1") (pin "11") (pinfunction "D8_11") (pintype "passive"))
    )
    (net (code "44") (name "Net-(J1-DB9)") (class "Default")
      (node (ref "J1") (pin "15") (pinfunction "DB9_15") (pintype "passive"))
      (node (ref "U1") (pin "12") (pinfunction "D9_12") (pintype "passive"))
    )
    (net (code "45") (name "Net-(J1-DB10)") (class "Default")
      (node (ref "J1") (pin "16") (pinfunction "DB10_16") (pintype "passive"))
      (node (ref "U1") (pin "13") (pinfunction "D10_13") (pintype "passive"))
    )
    (net (code "46") (name "Net-(J1-DB11)") (class "Default")
      (node (ref "J1") (pin "17") (pinfunction "DB11_17") (pintype "passive"))
      (node (ref "U1") (pin "14") (pinfunction "D11_14") (pintype "passive"))
    )
    (net (code "47") (name "Net-(J1-DB12)") (class "Default")
      (node (ref "J1") (pin "18") (pinfunction "DB12_18") (pintype "passive"))
      (node (ref "U1") (pin "15") (pinfunction "D12_15") (pintype "passive"))
    )
    (net (code "48") (name "Net-(J1-DB13)") (class "Default")
      (node (ref "J1") (pin "19") (pinfunction "DB13_19") (pintype "passive"))
      (node (ref "U1") (pin "16") (pinfunction "D13_16") (pintype "passive"))
    )
    (net (code "49") (name "Net-(J1-DB14)") (class "Default")
      (node (ref "J1") (pin "20") (pinfunction "DB14_20") (pintype "passive"))
      (node (ref "U1") (pin "17") (pinfunction "D14_17") (pintype "passive"))
    )
    (net (code "50") (name "Net-(J1-DB15)") (class "Default")
      (node (ref "J1") (pin "21") (pinfunction "DB15_21") (pintype "passive"))
      (node (ref "U1") (pin "18") (pinfunction "D15_18") (pintype "passive"))
    )
    (net (code "51") (name "Net-(J1-RD)") (class "Default")
      (node (ref "J1") (pin "4") (pinfunction "RD_4") (pintype "passive"))
      (node (ref "U1") (pin "22") (pinfunction "RD_22") (pintype "passive"))
    )
    (net (code "52") (name "Net-(J1-RS)") (class "Default")
      (node (ref "J1") (pin "2") (pinfunction "RS_2") (pintype "passive"))
      (node (ref "U1") (pin "20") (pinfunction "RS_20") (pintype "passive"))
    )
    (net (code "53") (name "Net-(J1-RST)") (class "Default")
      (node (ref "J1") (pin "5") (pinfunction "RST_5") (pintype "passive"))
      (node (ref "U1") (pin "23") (pinfunction "RST_23") (pintype "passive"))
    )
    (net (code "54") (name "Net-(J1-WR)") (class "Default")
      (node (ref "J1") (pin "3") (pinfunction "WR_3") (pintype "passive"))
      (node (ref "U1") (pin "21") (pinfunction "WR_21") (pintype "passive"))
    )
    (net (code "55") (name "Net-(J2-CD{slash}DAT3)") (class "Default")
      (node (ref "J2") (pin "2") (pinfunction "CD/DAT3_2") (pintype "passive"))
      (node (ref "R27") (pin "1") (pinfunction "1_1") (pintype "passive"))
      (node (ref "R32") (pin "2") (pinfunction "2_2") (pintype "passive"))
    )
    (net (code "56") (name "Net-(J2-CLK)") (class "Default")
      (node (ref "J2") (pin "5") (pinfunction "CLK_5") (pintype "passive"))
      (node (ref "R29") (pin "1") (pinfunction "1_1") (pintype "passive"))
      (node (ref "R30") (pin "2") (pinfunction "2_2") (pintype "passive"))
    )
    (net (code "57") (name "Net-(J2-CMD)") (class "Default")
      (node (ref "J2") (pin "3") (pinfunction "CMD_3") (pintype "passive"))
      (node (ref "R28") (pin "1") (pinfunction "1_1") (pintype "passive"))
      (node (ref "R31") (pin "2") (pinfunction "2_2") (pintype "passive"))
    )
    (net (code "58") (name "Net-(J3-6)") (class "Default")
      (node (ref "J3") (pin "3") (pinfunction "6_3") (pintype "passive"))
      (node (ref "X2") (pin "3") (pinfunction "3_3") (pintype "power_in"))
    )
    (net (code "59") (name "Net-(J3-7)") (class "Default")
      (node (ref "J3") (pin "2") (pinfunction "7_2") (pintype "passive"))
      (node (ref "X2") (pin "2") (pinfunction "2_2") (pintype "passive"))
    )
    (net (code "60") (name "Net-(J4-6)") (class "Default")
      (node (ref "J4") (pin "3") (pinfunction "6_3") (pintype "passive"))
      (node (ref "X2") (pin "5") (pinfunction "5_5") (pintype "power_in"))
    )
    (net (code "61") (name "Net-(J4-7)") (class "Default")
      (node (ref "J4") (pin "2") (pinfunction "7_2") (pintype "passive"))
      (node (ref "X2") (pin "4") (pinfunction "4_4") (pintype "power_in"))
    )
    (net (code "62") (name "Net-(L2-Pad1)") (class "Default")
      (node (ref "L2") (pin "1") (pinfunction "1_1") (pintype "passive"))
      (node (ref "U2") (pin "7") (pinfunction "SW_7") (pintype "passive"))
    )
    (net (code "63") (name "Net-(MOTHERBOARD1-1)") (class "Default")
      (node (ref "F2") (pin "2") (pinfunction "2_2") (pintype "passive"))
      (node (ref "MOTHERBOARD1") (pin "2") (pinfunction "1_2") (pintype "passive"))
    )
    (net (code "64") (name "Net-(R6-W)") (class "Default")
      (node (ref "R6") (pin "2") (pinfunction "W_2") (pintype "passive"))
      (node (ref "U3") (pin "1") (pinfunction "CH0_1") (pintype "passive"))
    )
    (net (code "65") (name "Net-(R7-W)") (class "Default")
      (node (ref "R7") (pin "2") (pinfunction "W_2") (pintype "passive"))
      (node (ref "U3") (pin "2") (pinfunction "CH1_2") (pintype "passive"))
    )
    (net (code "66") (name "Net-(R12-Pad1)") (class "Default")
      (node (ref "R12") (pin "1") (pinfunction "1_1") (pintype "passive"))
      (node (ref "R17") (pin "2") (pinfunction "2_2") (pintype "passive"))
      (node (ref "S3") (pin "1") (pinfunction "A_1") (pintype "passive"))
      (node (ref "S3") (pin "2") (pinfunction "A_2") (pintype "passive"))
    )
    (net (code "67") (name "Net-(R13-Pad1)") (class "Default")
      (node (ref "R13") (pin "1") (pinfunction "1_1") (pintype "passive"))
      (node (ref "R18") (pin "2") (pinfunction "2_2") (pintype "passive"))
      (node (ref "S2") (pin "1") (pinfunction "A_1") (pintype "passive"))
      (node (ref "S2") (pin "2") (pinfunction "A_2") (pintype "passive"))
    )
    (net (code "68") (name "Net-(R14-Pad1)") (class "Default")
      (node (ref "R14") (pin "1") (pinfunction "1_1") (pintype "passive"))
      (node (ref "R19") (pin "2") (pinfunction "2_2") (pintype "passive"))
      (node (ref "S4") (pin "1") (pinfunction "A_1") (pintype "passive"))
      (node (ref "S4") (pin "2") (pinfunction "A_2") (pintype "passive"))
    )
    (net (code "69") (name "Net-(R15-Pad1)") (class "Default")
      (node (ref "R15") (pin "1") (pinfunction "1_1") (pintype "passive"))
      (node (ref "R20") (pin "2") (pinfunction "2_2") (pintype "passive"))
      (node (ref "S5") (pin "1") (pinfunction "A_1") (pintype "passive"))
      (node (ref "S5") (pin "2") (pinfunction "A_2") (pintype "passive"))
    )
    (net (code "70") (name "Net-(R16-Pad1)") (class "Default")
      (node (ref "R16") (pin "1") (pinfunction "1_1") (pintype "passive"))
      (node (ref "X1") (pin "1") (pinfunction "1_1") (pintype "passive"))
    )
    (net (code "71") (name "Net-(R17-Pad1)") (class "Default")
      (node (ref "R17") (pin "1") (pinfunction "1_1") (pintype "passive"))
      (node (ref "R21") (pin "2") (pinfunction "2_2") (pintype "passive"))
      (node (ref "S7") (pin "1") (pinfunction "A_1") (pintype "passive"))
      (node (ref "S7") (pin "2") (pinfunction "A_2") (pintype "passive"))
    )
    (net (code "72") (name "Net-(R18-Pad1)") (class "Default")
      (node (ref "R18") (pin "1") (pinfunction "1_1") (pintype "passive"))
      (node (ref "R22") (pin "2") (pinfunction "2_2") (pintype "passive"))
      (node (ref "S6") (pin "1") (pinfunction "A_1") (pintype "passive"))
      (node (ref "S6") (pin "2") (pinfunction "A_2") (pintype "passive"))
    )
    (net (code "73") (name "Net-(R19-Pad1)") (class "Default")
      (node (ref "R19") (pin "1") (pinfunction "1_1") (pintype "passive"))
      (node (ref "R23") (pin "2") (pinfunction "2_2") (pintype "passive"))
      (node (ref "S8") (pin "1") (pinfunction "A_1") (pintype "passive"))
      (node (ref "S8") (pin "2") (pinfunction "A_2") (pintype "passive"))
    )
    (net (code "74") (name "Net-(R20-Pad1)") (class "Default")
      (node (ref "R20") (pin "1") (pinfunction "1_1") (pintype "passive"))
      (node (ref "R24") (pin "2") (pinfunction "2_2") (pintype "passive"))
      (node (ref "S9") (pin "1") (pinfunction "A_1") (pintype "passive"))
      (node (ref "S9") (pin "2") (pinfunction "A_2") (pintype "passive"))
    )
    (net (code "75") (name "Net-(R21-Pad1)") (class "Default")
      (node (ref "R21") (pin "1") (pinfunction "1_1") (pintype "passive"))
      (node (ref "S11") (pin "1") (pinfunction "A_1") (pintype "passive"))
      (node (ref "S11") (pin "2") (pinfunction "A_2") (pintype "passive"))
    )
    (net (code "76") (name "Net-(R22-Pad1)") (class "Default")
      (node (ref "R22") (pin "1") (pinfunction "1_1") (pintype "passive"))
      (node (ref "S10") (pin "1") (pinfunction "A_1") (pintype "passive"))
      (node (ref "S10") (pin "2") (pinfunction "A_2") (pintype "passive"))
    )
    (net (code "77") (name "Net-(R23-Pad1)") (class "Default")
      (node (ref "R23") (pin "1") (pinfunction "1_1") (pintype "passive"))
      (node (ref "S12") (pin "1") (pinfunction "A_1") (pintype "passive"))
      (node (ref "S12") (pin "2") (pinfunction "A_2") (pintype "passive"))
    )
    (net (code "78") (name "Net-(R25-Pad1)") (class "Default")
      (node (ref "R25") (pin "1") (pinfunction "1_1") (pintype "passive"))
      (node (ref "U4") (pin "1") (pinfunction "1_1") (pintype "passive"))
      (node (ref "X1") (pin "5") (pinfunction "5_5") (pintype "power_in"))
    )
    (net (code "79") (name "Net-(R26-Pad1)") (class "Default")
      (node (ref "R26") (pin "1") (pinfunction "1_1") (pintype "passive"))
      (node (ref "U5") (pin "1") (pinfunction "1_1") (pintype "passive"))
      (node (ref "X1") (pin "6") (pinfunction "6_6") (pintype "power_in"))
    )
    (net (code "80") (name "Net-(U2-VFB)") (class "Default")
      (node (ref "R1") (pin "2") (pinfunction "2_2") (pintype "passive"))
      (node (ref "R2") (pin "1") (pinfunction "1_1") (pintype "passive"))
      (node (ref "U2") (pin "3") (pinfunction "VFB_3") (pintype "passive"))
    )
    (net (code "81") (name "Net-(U3-CH4)") (class "Default")
      (node (ref "R15") (pin "2") (pinfunction "2_2") (pintype "passive"))
      (node (ref "R9") (pin "1") (pinfunction "1_1") (pintype "passive"))
      (node (ref "U3") (pin "5") (pinfunction "CH4_5") (pintype "passive"))
    )
    (net (code "82") (name "Net-(U3-CH5)") (class "Default")
      (node (ref "R11") (pin "1") (pinfunction "1_1") (pintype "passive"))
      (node (ref "R14") (pin "2") (pinfunction "2_2") (pintype "passive"))
      (node (ref "U3") (pin "6") (pinfunction "CH5_6") (pintype "passive"))
    )
    (net (code "83") (name "Net-(U3-CH6)") (class "Default")
      (node (ref "R10") (pin "1") (pinfunction "1_1") (pintype "passive"))
      (node (ref "R12") (pin "2") (pinfunction "2_2") (pintype "passive"))
      (node (ref "U3") (pin "7") (pinfunction "CH6_7") (pintype "passive"))
    )
    (net (code "84") (name "Net-(U3-CH7)") (class "Default")
      (node (ref "R13") (pin "2") (pinfunction "2_2") (pintype "passive"))
      (node (ref "R8") (pin "1") (pinfunction "1_1") (pintype "passive"))
      (node (ref "U3") (pin "8") (pinfunction "CH7_8") (pintype "passive"))
    )
    (net (code "85") (name "VCC12_IN") (class "Default")
      (node (ref "Q1") (pin "3") (pinfunction "S_3") (pintype "passive"))
      (node (ref "R3") (pin "2") (pinfunction "2_2") (pintype "passive"))
      (node (ref "R4") (pin "2") (pinfunction "2_2") (pintype "passive"))
      (node (ref "T1") (pin "LCP") (pinfunction "P2_LCP") (pintype "passive"))
    )
    (net (code "86") (name "unconnected-(ESP-1-GPIO0-Pad3)") (class "Default")
      (node (ref "ESP-1") (pin "3") (pinfunction "GPIO0_3") (pintype "passive"))
    )
    (net (code "87") (name "unconnected-(ESP-1-GPIO2-Pad2)") (class "Default")
      (node (ref "ESP-1") (pin "2") (pinfunction "GPIO2_2") (pintype "passive"))
    )
    (net (code "88") (name "unconnected-(ESP-1-GPIO16-Pad7)") (class "Default")
      (node (ref "ESP-1") (pin "7") (pinfunction "GPIO16_7") (pintype "passive"))
    )
    (net (code "89") (name "unconnected-(J2-DAT1-Pad8)") (class "Default")
      (node (ref "J2") (pin "8") (pinfunction "DAT1_8") (pintype "passive"))
    )
    (net (code "90") (name "unconnected-(J2-DAT2-Pad1)") (class "Default")
      (node (ref "J2") (pin "1") (pinfunction "DAT2_1") (pintype "passive"))
    )
    (net (code "91") (name "unconnected-(J3-4-Pad5)") (class "Default")
      (node (ref "J3") (pin "5") (pinfunction "4_5") (pintype "passive"))
    )
    (net (code "92") (name "unconnected-(J3-5-Pad4)") (class "Default")
      (node (ref "J3") (pin "4") (pinfunction "5_4") (pintype "passive"))
    )
    (net (code "93") (name "unconnected-(J4-4-Pad5)") (class "Default")
      (node (ref "J4") (pin "5") (pinfunction "4_5") (pintype "passive"))
    )
    (net (code "94") (name "unconnected-(J4-5-Pad4)") (class "Default")
      (node (ref "J4") (pin "4") (pinfunction "5_4") (pintype "passive"))
    )
    (net (code "95") (name "unconnected-(J5-4-Pad5)") (class "Default")
      (node (ref "J5") (pin "5") (pinfunction "4_5") (pintype "passive"))
    )
    (net (code "96") (name "unconnected-(J5-5-Pad4)") (class "Default")
      (node (ref "J5") (pin "4") (pinfunction "5_4") (pintype "passive"))
    )
    (net (code "97") (name "unconnected-(U1-INT-Pad28)") (class "Default")
      (node (ref "U1") (pin "28") (pinfunction "INT_28") (pintype "passive"))
    )
    (net (code "98") (name "unconnected-(U1-NC-Pad1)") (class "Default")
      (node (ref "U1") (pin "1") (pinfunction "NC_1") (pintype "passive"))
    )
    (net (code "99") (name "unconnected-(U1-NC-Pad24)") (class "Default")
      (node (ref "U1") (pin "24") (pinfunction "NC_24") (pintype "passive"))
    )
    (net (code "100") (name "unconnected-(U1-NC-Pad27)") (class "Default")
      (node (ref "U1") (pin "27") (pinfunction "NC_27") (pintype "passive"))
    )
    (net (code "101") (name "unconnected-(U1-WAIT-Pad29)") (class "Default")
      (node (ref "U1") (pin "29") (pinfunction "WAIT_29") (pintype "passive"))
    )
    (net (code "102") (name "unconnected-(X2-Pad6)") (class "Default")
      (node (ref "X2") (pin "6") (pinfunction "6_6") (pintype "power_in"))
    )
  )
)
